# 105358-3SC002-01-A_PWR_MGMT.net
KiCad netlist of a schematic drawn in Altium Designer
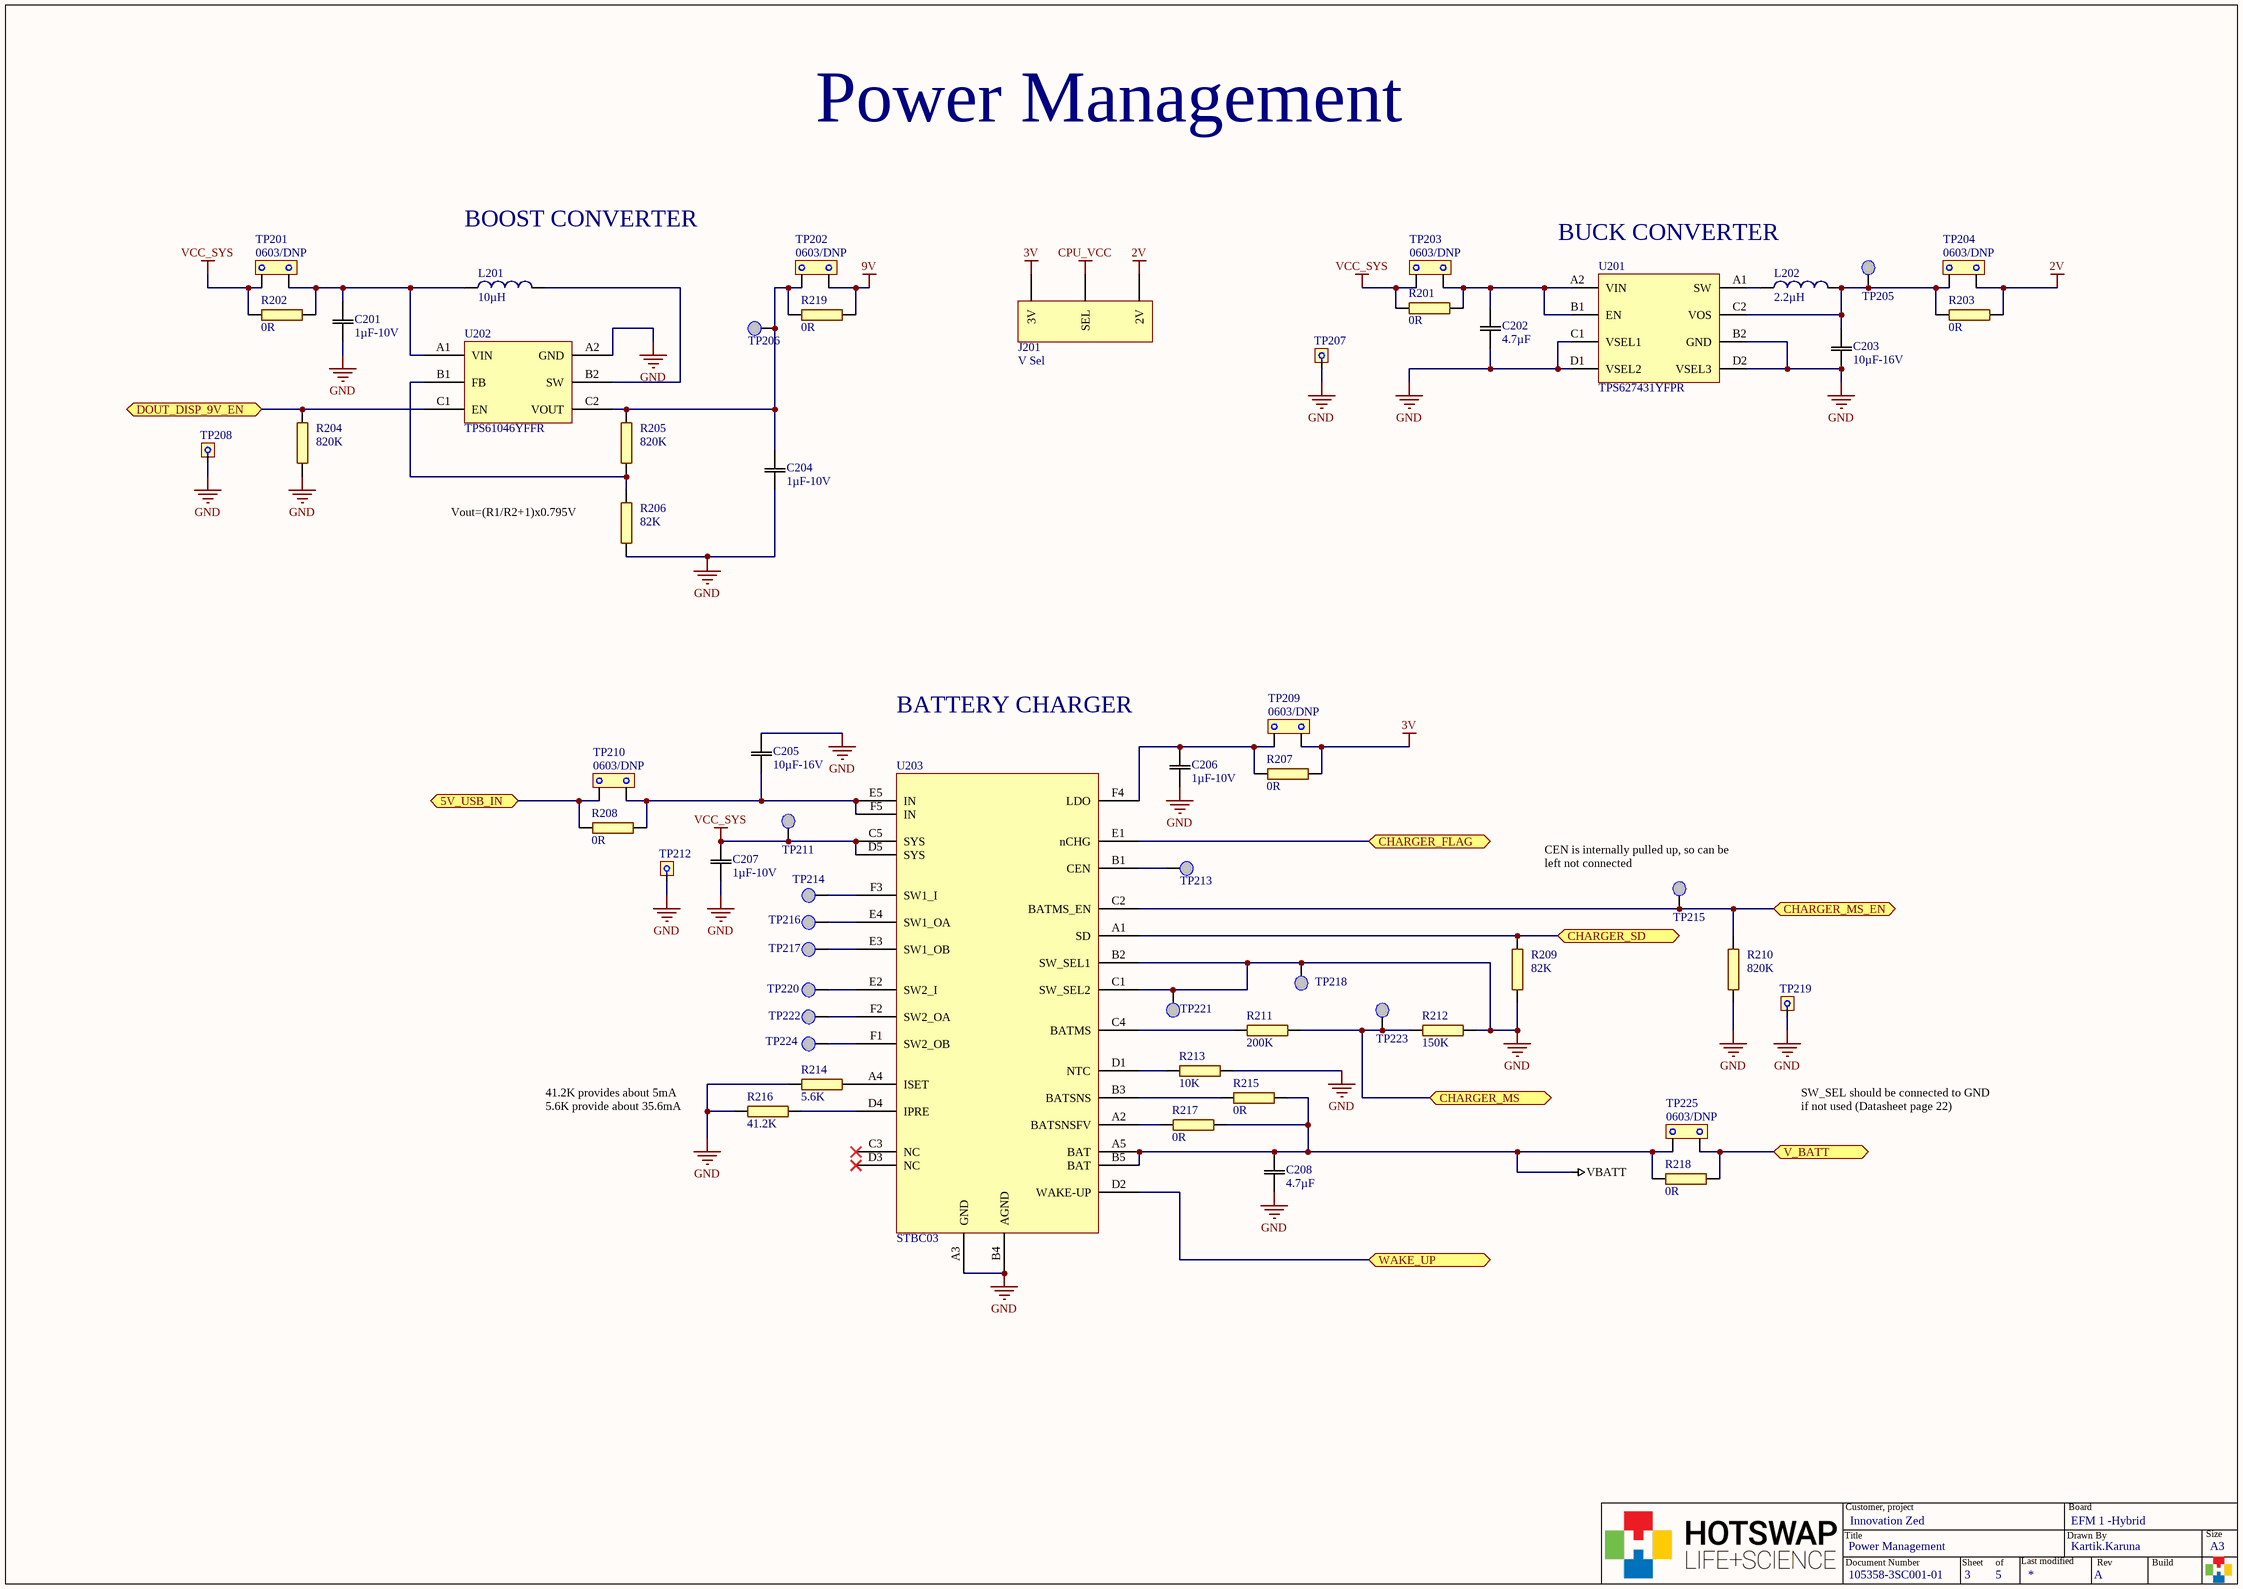
[diagram p0: 105358-3SC002-01-A_PWR_MGMT.SchDoc]

(export (version "E")
  (design (tool "Eeschema 10.0.6"))
  (components
    (comp (ref "C201")
      (value "1µF-10V")
      (footprint "0402C_HIGH_DENSITY")
      (description "1µF ±10% 10V X5R Ceramic Capacitor 0402")
      (fields
        (field (name "MANUFACTURER PART NUMBER") "CC0402KRX5R6BB105")
        (field (name "MANUFACTURER") "Yageo")
      )
      (libsource (lib "ConnectMedical") (part "0402C-1uF-10V"))
    )
    (comp (ref "C202")
      (value "4.7µF")
      (footprint "0402C_HIGH_DENSITY")
      (description "4.7µF ±10% 6.3V X5R Ceramic Capacitor 0402")
      (fields
        (field (name "MANUFACTURER PART NUMBER") "C1005X5R0J475K050BC")
        (field (name "MANUFACTURER") "TDK Corporation")
      )
      (libsource (lib "ConnectMedical") (part "0402C-4.7uF-6.3V"))
    )
    (comp (ref "C203")
      (value "10µF-16V")
      (footprint "0603C_HIGH_DENSITY")
      (description "16µF ±10% 16V X5R Ceramic Capacitor 0603")
      (fields
        (field (name "MANUFACTURER PART NUMBER") "GRT188R61C106KE13D")
        (field (name "MANUFACTURER") "Murata Electronics North America")
      )
      (libsource (lib "ConnectMedical") (part "0603C-10uF-16V"))
    )
    (comp (ref "C204")
      (value "1µF-10V")
      (footprint "0402C_HIGH_DENSITY")
      (description "1µF ±10% 10V X5R Ceramic Capacitor 0402")
      (fields
        (field (name "MANUFACTURER PART NUMBER") "CC0402KRX5R6BB105")
        (field (name "MANUFACTURER") "Yageo")
      )
      (libsource (lib "ConnectMedical") (part "0402C-1uF-10V"))
    )
    (comp (ref "C205")
      (value "10µF-16V")
      (footprint "0603C_HIGH_DENSITY")
      (description "16µF ±10% 16V X5R Ceramic Capacitor 0603")
      (fields
        (field (name "MANUFACTURER PART NUMBER") "GRT188R61C106KE13D")
        (field (name "MANUFACTURER") "Murata Electronics North America")
      )
      (libsource (lib "ConnectMedical") (part "0603C-10uF-16V"))
    )
    (comp (ref "C206")
      (value "1µF-10V")
      (footprint "0402C_HIGH_DENSITY")
      (description "1µF ±10% 10V X5R Ceramic Capacitor 0402")
      (fields
        (field (name "MANUFACTURER PART NUMBER") "CC0402KRX5R6BB105")
        (field (name "MANUFACTURER") "Yageo")
      )
      (libsource (lib "ConnectMedical") (part "0402C-1uF-10V"))
    )
    (comp (ref "C207")
      (value "1µF-10V")
      (footprint "0402C_HIGH_DENSITY")
      (description "1µF ±10% 10V X5R Ceramic Capacitor 0402")
      (fields
        (field (name "MANUFACTURER PART NUMBER") "CC0402KRX5R6BB105")
        (field (name "MANUFACTURER") "Yageo")
      )
      (libsource (lib "ConnectMedical") (part "0402C-1uF-10V"))
    )
    (comp (ref "C208")
      (value "4.7µF")
      (footprint "0402C_HIGH_DENSITY")
      (description "4.7µF ±10% 6.3V X5R Ceramic Capacitor 0402")
      (fields
        (field (name "MANUFACTURER PART NUMBER") "C1005X5R0J475K050BC")
        (field (name "MANUFACTURER") "TDK Corporation")
      )
      (libsource (lib "ConnectMedical") (part "0402C-4.7uF-6.3V"))
    )
    (comp (ref "J201")
      (value "V Sel")
      (footprint "Pin Header 3 x 1 - 2.54mm")
      (libsource (lib "ConnectMedical") (part "CPU_V_SEL"))
    )
    (comp (ref "L201")
      (value "10µH")
      (footprint "0805L_HIGH_DENSITY")
      (description "FIXED IND 10UH 500MA 300 MOHM")
      (fields
        (field (name "DIGI-KEY PART NUMBER") "445-6762-1-ND")
        (field (name "MANUFACTURER") "TDK Corporation")
      )
      (libsource (lib "ConnectMedical") (part "0805L-10uH-0.39Ohm"))
    )
    (comp (ref "L202")
      (value "2.2µH")
      (footprint "0805L_HIGH_DENSITY")
      (description "FIXED IND 2.2UH 600MA 0.2OHM SMD")
      (fields
        (field (name "DIGI-KEY PART NUMBER") "445-17077-1-ND")
        (field (name "MANUFACTURER") "TDK Corporation")
      )
      (libsource (lib "ConnectMedical") (part "0805L-2.2uH-0.2Ohm"))
    )
    (comp (ref "R201")
      (value "0R")
      (footprint "0603R-GENRIC")
      (description "RES SMD 0 OHM 1% 1/10W 0603")
      (fields (field (name "POWER") "0.063W"))
      (libsource (lib "ConnectMedical") (part "0603R-0R -1%-0.063W"))
    )
    (comp (ref "R202")
      (value "0R")
      (footprint "0603R-GENRIC")
      (description "RES SMD 0 OHM 1% 1/10W 0603")
      (fields (field (name "POWER") "0.063W"))
      (libsource (lib "ConnectMedical") (part "0603R-0R -1%-0.063W"))
    )
    (comp (ref "R203")
      (value "0R")
      (footprint "0603R-GENRIC")
      (description "RES SMD 0 OHM 1% 1/10W 0603")
      (fields (field (name "POWER") "0.063W"))
      (libsource (lib "ConnectMedical") (part "0603R-0R -1%-0.063W"))
    )
    (comp (ref "R204")
      (value "820K")
      (footprint "0402R-GENERIC")
      (description "RES SMD 820kOHM 1% 1/16W 0402")
      (fields (field (name "DIGI-KEY PART NUMBER") "YAG3240CT-ND") (field (name "MANUFACTURER") "Yageo"))
      (libsource (lib "ConnectMedical") (part "0402R-820k OHM-1%-0.063W"))
    )
    (comp (ref "R205")
      (value "820K")
      (footprint "0402R-GENERIC")
      (description "RES SMD 820kOHM 1% 1/16W 0402")
      (fields (field (name "DIGI-KEY PART NUMBER") "YAG3240CT-ND") (field (name "MANUFACTURER") "Yageo"))
      (libsource (lib "ConnectMedical") (part "0402R-820k OHM-1%-0.063W"))
    )
    (comp (ref "R206")
      (value "82K")
      (footprint "0402R-GENERIC")
      (description "RES SMD 82kOHM 1% 1/16W 0402")
      (fields (field (name "DIGI-KEY PART NUMBER") "311-82.0KLRCT-ND") (field (name "MANUFACTURER") "Yageo"))
      (libsource (lib "ConnectMedical") (part "0402R-82k OHM-1%-0.063W"))
    )
    (comp (ref "R207")
      (value "0R")
      (footprint "0603R-GENRIC")
      (description "RES SMD 0 OHM 1% 1/10W 0603")
      (fields (field (name "POWER") "0.063W"))
      (libsource (lib "ConnectMedical") (part "0603R-0R -1%-0.063W"))
    )
    (comp (ref "R208")
      (value "0R")
      (footprint "0603R-GENRIC")
      (description "RES SMD 0 OHM 1% 1/10W 0603")
      (fields (field (name "POWER") "0.063W"))
      (libsource (lib "ConnectMedical") (part "0603R-0R -1%-0.063W"))
    )
    (comp (ref "R209")
      (value "82K")
      (footprint "0402R-GENERIC")
      (description "RES SMD 82kOHM 1% 1/16W 0402")
      (fields (field (name "DIGI-KEY PART NUMBER") "311-82.0KLRCT-ND") (field (name "MANUFACTURER") "Yageo"))
      (libsource (lib "ConnectMedical") (part "0402R-82k OHM-1%-0.063W"))
    )
    (comp (ref "R210")
      (value "820K")
      (footprint "0402R-GENERIC")
      (description "RES SMD 820kOHM 1% 1/16W 0402")
      (fields (field (name "DIGI-KEY PART NUMBER") "YAG3240CT-ND") (field (name "MANUFACTURER") "Yageo"))
      (libsource (lib "ConnectMedical") (part "0402R-820k OHM-1%-0.063W"))
    )
    (comp (ref "R211")
      (value "200K")
      (footprint "0402R-GENERIC")
      (description "RES SMD 200kOHM 1% 1/16W 0402")
      (fields (field (name "DIGI-KEY PART NUMBER") "YAG3452CT-ND") (field (name "MANUFACTURER") "Yageo"))
      (libsource (lib "ConnectMedical") (part "0402R-200k OHM-1%-0.063W"))
    )
    (comp (ref "R212")
      (value "150K")
      (footprint "0402R-GENERIC")
      (description "RES SMD 150kOHM 5% 1/16W 0402")
      (fields (field (name "DIGI-KEY PART NUMBER") "311-150KJRCT-ND") (field (name "MANUFACTURER") "Yageo"))
      (libsource (lib "ConnectMedical") (part "0402R-150k OHM-5%-0.063W"))
    )
    (comp (ref "R213")
      (value "10K")
      (footprint "0402R-GENERIC")
      (description "RES SMD 10kOHM 1% 1/16W 0402")
      (fields (field (name "DIGI-KEY PART NUMBER") "311-10.0KLRCT-ND") (field (name "MANUFACTURER") "Yageo"))
      (libsource (lib "ConnectMedical") (part "0402R-10k OHM-1%-0.063W"))
    )
    (comp (ref "R214")
      (value "5.6K")
      (footprint "0603R-GENRIC")
      (description "RES SMD 5.6kOHM 5% 1/16W 0603")
      (fields (field (name "MANUFACTURER") "Yageo") (field (name "TOLERANCE") "5%"))
      (libsource (lib "ConnectMedical") (part "0603R-5.6k OHM-5%-0.063W"))
    )
    (comp (ref "R215")
      (value "0R")
      (footprint "0603R-GENRIC")
      (description "RES SMD 0 OHM 1% 1/10W 0603")
      (fields (field (name "POWER") "0.063W"))
      (libsource (lib "ConnectMedical") (part "0603R-0R -1%-0.063W"))
    )
    (comp (ref "R216")
      (value "41.2K")
      (footprint "0603R-GENRIC")
      (description "RES SMD 41.2kOHM 1% 0603")
      (fields (field (name "MANUFACTURER") "Yageo") (field (name "TOLERANCE") "1%"))
      (libsource (lib "ConnectMedical") (part "0603R-41.2k OHM-1%"))
    )
    (comp (ref "R217")
      (value "0R")
      (footprint "0603R-GENRIC")
      (description "RES SMD 0 OHM 1% 1/10W 0603")
      (fields (field (name "POWER") "0.063W"))
      (libsource (lib "ConnectMedical") (part "0603R-0R -1%-0.063W"))
    )
    (comp (ref "R218")
      (value "0R")
      (footprint "0603R-GENRIC")
      (description "RES SMD 0 OHM 1% 1/10W 0603")
      (fields (field (name "POWER") "0.063W"))
      (libsource (lib "ConnectMedical") (part "0603R-0R -1%-0.063W"))
    )
    (comp (ref "R219")
      (value "0R")
      (footprint "0603R-GENRIC")
      (description "RES SMD 0 OHM 1% 1/10W 0603")
      (fields (field (name "POWER") "0.063W"))
      (libsource (lib "ConnectMedical") (part "0603R-0R -1%-0.063W"))
    )
    (comp (ref "TP201")
      (value "0603/DNP")
      (footprint "TESTPOINT_C_R0608")
      (description "Test point for Med Current 0402 JUMPER SMD O OHM 1% 1/4W 0603")
      (libsource (lib "ConnectMedical") (part "TP_C_R0603"))
    )
    (comp (ref "TP202")
      (value "0603/DNP")
      (footprint "TESTPOINT_C_R0608")
      (description "Test point for Med Current 0402 JUMPER SMD O OHM 1% 1/4W 0603")
      (libsource (lib "ConnectMedical") (part "TP_C_R0603"))
    )
    (comp (ref "TP203")
      (value "0603/DNP")
      (footprint "TESTPOINT_C_R0608")
      (description "Test point for Med Current 0402 JUMPER SMD O OHM 1% 1/4W 0603")
      (libsource (lib "ConnectMedical") (part "TP_C_R0603"))
    )
    (comp (ref "TP204")
      (value "0603/DNP")
      (footprint "TESTPOINT_C_R0608")
      (description "Test point for Med Current 0402 JUMPER SMD O OHM 1% 1/4W 0603")
      (libsource (lib "ConnectMedical") (part "TP_C_R0603"))
    )
    (comp (ref "TP205")
      (value "TEST POINT")
      (footprint "PAD TEST POINT")
      (description "Testing Poiny")
      (libsource (lib "ConnectMedical") (part "TEST POINT"))
    )
    (comp (ref "TP206")
      (value "TEST POINT")
      (footprint "PAD TEST POINT")
      (description "Testing Poiny")
      (libsource (lib "ConnectMedical") (part "TEST POINT"))
    )
    (comp (ref "TP207")
      (value "TP_V_HOOK")
      (footprint "Testpoint_Hook")
      (description "Black PC Test Point")
      (fields
        (field (name "DIGI-KEY PART NUMBER") "36-5001-ND")
        (field (name "MANUFACTURER") "Keystone Electronics")
      )
      (libsource (lib "ConnectMedical") (part "TP_V_HOOK"))
    )
    (comp (ref "TP208")
      (value "TP_V_HOOK")
      (footprint "Testpoint_Hook")
      (description "Black PC Test Point")
      (fields
        (field (name "DIGI-KEY PART NUMBER") "36-5001-ND")
        (field (name "MANUFACTURER") "Keystone Electronics")
      )
      (libsource (lib "ConnectMedical") (part "TP_V_HOOK"))
    )
    (comp (ref "TP209")
      (value "0603/DNP")
      (footprint "TESTPOINT_C_R0608")
      (description "Test point for Med Current 0402 JUMPER SMD O OHM 1% 1/4W 0603")
      (libsource (lib "ConnectMedical") (part "TP_C_R0603"))
    )
    (comp (ref "TP210")
      (value "0603/DNP")
      (footprint "TESTPOINT_C_R0608")
      (description "Test point for Med Current 0402 JUMPER SMD O OHM 1% 1/4W 0603")
      (libsource (lib "ConnectMedical") (part "TP_C_R0603"))
    )
    (comp (ref "TP211")
      (value "TEST POINT")
      (footprint "PAD TEST POINT")
      (description "Testing Poiny")
      (libsource (lib "ConnectMedical") (part "TEST POINT"))
    )
    (comp (ref "TP212")
      (value "TP_V_HOOK")
      (footprint "Testpoint_Hook")
      (description "Black PC Test Point")
      (fields
        (field (name "DIGI-KEY PART NUMBER") "36-5001-ND")
        (field (name "MANUFACTURER") "Keystone Electronics")
      )
      (libsource (lib "ConnectMedical") (part "TP_V_HOOK"))
    )
    (comp (ref "TP213")
      (value "TEST POINT")
      (footprint "PAD TEST POINT")
      (description "Testing Poiny")
      (libsource (lib "ConnectMedical") (part "TEST POINT"))
    )
    (comp (ref "TP214")
      (value "TEST POINT")
      (footprint "PAD TEST POINT")
      (description "Testing Poiny")
      (libsource (lib "ConnectMedical") (part "TEST POINT"))
    )
    (comp (ref "TP215")
      (value "TEST POINT")
      (footprint "PAD TEST POINT")
      (description "Testing Poiny")
      (libsource (lib "ConnectMedical") (part "TEST POINT"))
    )
    (comp (ref "TP216")
      (value "TEST POINT")
      (footprint "PAD TEST POINT")
      (description "Testing Poiny")
      (libsource (lib "ConnectMedical") (part "TEST POINT"))
    )
    (comp (ref "TP217")
      (value "TEST POINT")
      (footprint "PAD TEST POINT")
      (description "Testing Poiny")
      (libsource (lib "ConnectMedical") (part "TEST POINT"))
    )
    (comp (ref "TP218")
      (value "TEST POINT")
      (footprint "PAD TEST POINT")
      (description "Testing Poiny")
      (libsource (lib "ConnectMedical") (part "TEST POINT"))
    )
    (comp (ref "TP219")
      (value "TP_V_HOOK")
      (footprint "Testpoint_Hook")
      (description "Black PC Test Point")
      (fields
        (field (name "DIGI-KEY PART NUMBER") "36-5001-ND")
        (field (name "MANUFACTURER") "Keystone Electronics")
      )
      (libsource (lib "ConnectMedical") (part "TP_V_HOOK"))
    )
    (comp (ref "TP220")
      (value "TEST POINT")
      (footprint "PAD TEST POINT")
      (description "Testing Poiny")
      (libsource (lib "ConnectMedical") (part "TEST POINT"))
    )
    (comp (ref "TP221")
      (value "TEST POINT")
      (footprint "PAD TEST POINT")
      (description "Testing Poiny")
      (libsource (lib "ConnectMedical") (part "TEST POINT"))
    )
    (comp (ref "TP222")
      (value "TEST POINT")
      (footprint "PAD TEST POINT")
      (description "Testing Poiny")
      (libsource (lib "ConnectMedical") (part "TEST POINT"))
    )
    (comp (ref "TP223")
      (value "TEST POINT")
      (footprint "PAD TEST POINT")
      (description "Testing Poiny")
      (libsource (lib "ConnectMedical") (part "TEST POINT"))
    )
    (comp (ref "TP224")
      (value "TEST POINT")
      (footprint "PAD TEST POINT")
      (description "Testing Poiny")
      (libsource (lib "ConnectMedical") (part "TEST POINT"))
    )
    (comp (ref "TP225")
      (value "0603/DNP")
      (footprint "TESTPOINT_C_R0608")
      (description "Test point for Med Current 0402 JUMPER SMD O OHM 1% 1/4W 0603")
      (libsource (lib "ConnectMedical") (part "TP_C_R0603"))
    )
    (comp (ref "U201")
      (value "TPS627431YFPR")
      (footprint "TPS627431YFPR")
      (description "Buck Converter")
      (fields
        (field (name "MANUFACTURER") "Texas Instruments")
        (field (name "DIGI-KEY PART NUMBER") "296-44499-2-ND")
      )
      (libsource (lib "ConnectMedical") (part "TPS627431YFPR"))
    )
    (comp (ref "U202")
      (value "TPS61046YFFR")
      (footprint "TPS61046YFFR")
      (description "Boost converter 28V")
      (fields
        (field (name "MANUFACTURER") "Texas Instruments")
        (field (name "DIGI-KEY PART NUMBER") "296-44337-1-ND")
      )
      (libsource (lib "ConnectMedical") (part "TPS61046YFFR"))
    )
    (comp (ref "U203")
      (value "STBC03")
      (footprint "STBC03")
      (description "Li-Ion linear battery charger")
      (fields
        (field (name "MANUFACTURER PART NUMBER") "STBC03JR")
        (field (name "MANUFACTURER") "STMicroelectronics")
      )
      (libsource (lib "ConnectMedical") (part "STBC03"))
    )
  )
  (nets
    (net (code "1") (name "/5V_USB_IN") (class "Default")
      (node (ref "R208") (pin "1") (pintype "passive"))
      (node (ref "TP210") (pin "1") (pintype "power_in"))
    )
    (net (code "2") (name "/CHARGER_FLAG") (class "Default")
      (node (ref "U203") (pin "E1") (pinfunction "nCHG_E1") (pintype "passive"))
    )
    (net (code "3") (name "/CHARGER_MS") (class "Default")
      (node (ref "R211") (pin "2") (pintype "passive"))
      (node (ref "R212") (pin "1") (pintype "passive"))
      (node (ref "TP223") (pin "1") (pinfunction "Test_Point_1") (pintype "passive"))
    )
    (net (code "4") (name "/CHARGER_MS_EN") (class "Default")
      (node (ref "R210") (pin "1") (pintype "passive"))
      (node (ref "TP215") (pin "1") (pinfunction "Test_Point_1") (pintype "passive"))
      (node (ref "U203") (pin "C2") (pinfunction "BATMS_EN_C2") (pintype "passive"))
    )
    (net (code "5") (name "/CHARGER_SD") (class "Default")
      (node (ref "R209") (pin "1") (pintype "passive"))
      (node (ref "U203") (pin "A1") (pinfunction "SD_A1") (pintype "passive"))
    )
    (net (code "6") (name "/DOUT_DISP_9V_EN") (class "Default")
      (node (ref "R204") (pin "1") (pintype "passive"))
      (node (ref "U202") (pin "C1") (pinfunction "EN_C1") (pintype "passive"))
    )
    (net (code "7") (name "/V_BATT") (class "Default")
      (node (ref "R218") (pin "2") (pintype "passive"))
      (node (ref "TP225") (pin "2") (pintype "power_in"))
    )
    (net (code "8") (name "/WAKE_UP") (class "Default")
      (node (ref "U203") (pin "D2") (pinfunction "WAKE-UP_D2") (pintype "passive"))
    )
    (net (code "9") (name "2V") (class "Default")
      (node (ref "J201") (pin "3") (pinfunction "2V_3") (pintype "power_in"))
      (node (ref "R203") (pin "2") (pintype "passive"))
      (node (ref "TP204") (pin "2") (pintype "power_in"))
    )
    (net (code "10") (name "3V") (class "Default")
      (node (ref "J201") (pin "1") (pinfunction "3V_1") (pintype "power_in"))
      (node (ref "R207") (pin "2") (pintype "passive"))
      (node (ref "TP209") (pin "2") (pintype "power_in"))
    )
    (net (code "11") (name "9V") (class "Default")
      (node (ref "R219") (pin "2") (pintype "passive"))
      (node (ref "TP202") (pin "2") (pintype "power_in"))
    )
    (net (code "12") (name "CPU_VCC") (class "Default")
      (node (ref "J201") (pin "2") (pinfunction "SEL_2") (pintype "power_in"))
    )
    (net (code "13") (name "GND") (class "Default")
      (node (ref "C201") (pin "1") (pinfunction "1_1") (pintype "passive"))
      (node (ref "C202") (pin "1") (pinfunction "1_1") (pintype "passive"))
      (node (ref "C203") (pin "1") (pinfunction "1_1") (pintype "passive"))
      (node (ref "C204") (pin "1") (pinfunction "1_1") (pintype "passive"))
      (node (ref "C205") (pin "2") (pinfunction "2_2") (pintype "passive"))
      (node (ref "C206") (pin "1") (pinfunction "1_1") (pintype "passive"))
      (node (ref "C207") (pin "1") (pinfunction "1_1") (pintype "passive"))
      (node (ref "C208") (pin "1") (pinfunction "1_1") (pintype "passive"))
      (node (ref "R204") (pin "2") (pintype "passive"))
      (node (ref "R206") (pin "2") (pintype "passive"))
      (node (ref "R209") (pin "2") (pintype "passive"))
      (node (ref "R210") (pin "2") (pintype "passive"))
      (node (ref "R212") (pin "2") (pintype "passive"))
      (node (ref "R213") (pin "2") (pintype "passive"))
      (node (ref "R214") (pin "1") (pintype "passive"))
      (node (ref "R216") (pin "1") (pintype "passive"))
      (node (ref "TP207") (pin "1") (pinfunction "8_1") (pintype "passive"))
      (node (ref "TP208") (pin "1") (pinfunction "8_1") (pintype "passive"))
      (node (ref "TP212") (pin "1") (pinfunction "8_1") (pintype "passive"))
      (node (ref "TP218") (pin "1") (pinfunction "Test_Point_1") (pintype "passive"))
      (node (ref "TP219") (pin "1") (pinfunction "8_1") (pintype "passive"))
      (node (ref "TP221") (pin "1") (pinfunction "Test_Point_1") (pintype "passive"))
      (node (ref "U201") (pin "B2") (pinfunction "GND_B2") (pintype "passive"))
      (node (ref "U201") (pin "C1") (pinfunction "VSEL1_C1") (pintype "passive"))
      (node (ref "U201") (pin "D1") (pinfunction "VSEL2_D1") (pintype "passive"))
      (node (ref "U201") (pin "D2") (pinfunction "VSEL3_D2") (pintype "passive"))
      (node (ref "U202") (pin "A2") (pinfunction "GND_A2") (pintype "passive"))
      (node (ref "U203") (pin "A3") (pinfunction "GND_A3") (pintype "passive"))
      (node (ref "U203") (pin "B2") (pinfunction "SW_SEL1_B2") (pintype "passive"))
      (node (ref "U203") (pin "B4") (pinfunction "AGND_B4") (pintype "passive"))
      (node (ref "U203") (pin "C1") (pinfunction "SW_SEL2_C1") (pintype "passive"))
    )
    (net (code "14") (name "Net-(C205-Pad1)") (class "Default")
      (node (ref "C205") (pin "1") (pinfunction "1_1") (pintype "passive"))
      (node (ref "R208") (pin "2") (pintype "passive"))
      (node (ref "TP210") (pin "2") (pintype "power_in"))
      (node (ref "U203") (pin "E5") (pinfunction "IN_E5") (pintype "passive"))
      (node (ref "U203") (pin "F5") (pinfunction "IN_F5") (pintype "passive"))
    )
    (net (code "15") (name "Net-(TP205-Test_Point)") (class "Default")
      (node (ref "C203") (pin "2") (pinfunction "2_2") (pintype "passive"))
      (node (ref "L202") (pin "2") (pinfunction "2_2") (pintype "passive"))
      (node (ref "R203") (pin "1") (pintype "passive"))
      (node (ref "TP204") (pin "1") (pintype "power_in"))
      (node (ref "TP205") (pin "1") (pinfunction "Test_Point_1") (pintype "passive"))
      (node (ref "U201") (pin "C2") (pinfunction "VOS_C2") (pintype "passive"))
    )
    (net (code "16") (name "Net-(TP206-Test_Point)") (class "Default")
      (node (ref "C204") (pin "2") (pinfunction "2_2") (pintype "passive"))
      (node (ref "R205") (pin "1") (pintype "passive"))
      (node (ref "R219") (pin "1") (pintype "passive"))
      (node (ref "TP202") (pin "1") (pintype "power_in"))
      (node (ref "TP206") (pin "1") (pinfunction "Test_Point_1") (pintype "passive"))
      (node (ref "U202") (pin "C2") (pinfunction "VOUT_C2") (pintype "passive"))
    )
    (net (code "17") (name "Net-(TP213-Test_Point)") (class "Default")
      (node (ref "TP213") (pin "1") (pinfunction "Test_Point_1") (pintype "passive"))
      (node (ref "U203") (pin "B1") (pinfunction "CEN_B1") (pintype "passive"))
    )
    (net (code "18") (name "Net-(TP214-Test_Point)") (class "Default")
      (node (ref "TP214") (pin "1") (pinfunction "Test_Point_1") (pintype "passive"))
      (node (ref "U203") (pin "F3") (pinfunction "SW1_I_F3") (pintype "passive"))
    )
    (net (code "19") (name "Net-(TP216-Test_Point)") (class "Default")
      (node (ref "TP216") (pin "1") (pinfunction "Test_Point_1") (pintype "passive"))
      (node (ref "U203") (pin "E4") (pinfunction "SW1_OA_E4") (pintype "passive"))
    )
    (net (code "20") (name "Net-(TP217-Test_Point)") (class "Default")
      (node (ref "TP217") (pin "1") (pinfunction "Test_Point_1") (pintype "passive"))
      (node (ref "U203") (pin "E3") (pinfunction "SW1_OB_E3") (pintype "passive"))
    )
    (net (code "21") (name "Net-(TP220-Test_Point)") (class "Default")
      (node (ref "TP220") (pin "1") (pinfunction "Test_Point_1") (pintype "passive"))
      (node (ref "U203") (pin "E2") (pinfunction "SW2_I_E2") (pintype "passive"))
    )
    (net (code "22") (name "Net-(TP222-Test_Point)") (class "Default")
      (node (ref "TP222") (pin "1") (pinfunction "Test_Point_1") (pintype "passive"))
      (node (ref "U203") (pin "F2") (pinfunction "SW2_OA_F2") (pintype "passive"))
    )
    (net (code "23") (name "Net-(TP224-Test_Point)") (class "Default")
      (node (ref "TP224") (pin "1") (pinfunction "Test_Point_1") (pintype "passive"))
      (node (ref "U203") (pin "F1") (pinfunction "SW2_OB_F1") (pintype "passive"))
    )
    (net (code "24") (name "Net-(U201-EN)") (class "Default")
      (node (ref "C202") (pin "2") (pinfunction "2_2") (pintype "passive"))
      (node (ref "R201") (pin "2") (pintype "passive"))
      (node (ref "TP203") (pin "2") (pintype "power_in"))
      (node (ref "U201") (pin "A2") (pinfunction "VIN_A2") (pintype "passive"))
      (node (ref "U201") (pin "B1") (pinfunction "EN_B1") (pintype "passive"))
    )
    (net (code "25") (name "Net-(U201-SW)") (class "Default")
      (node (ref "L202") (pin "1") (pinfunction "1_1") (pintype "passive"))
      (node (ref "U201") (pin "A1") (pinfunction "SW_A1") (pintype "passive"))
    )
    (net (code "26") (name "Net-(U202-FB)") (class "Default")
      (node (ref "R205") (pin "2") (pintype "passive"))
      (node (ref "R206") (pin "1") (pintype "passive"))
      (node (ref "U202") (pin "B1") (pinfunction "FB_B1") (pintype "passive"))
    )
    (net (code "27") (name "Net-(U202-SW)") (class "Default")
      (node (ref "L201") (pin "2") (pinfunction "2_2") (pintype "passive"))
      (node (ref "U202") (pin "B2") (pinfunction "SW_B2") (pintype "passive"))
    )
    (net (code "28") (name "Net-(U202-VIN)") (class "Default")
      (node (ref "C201") (pin "2") (pinfunction "2_2") (pintype "passive"))
      (node (ref "L201") (pin "1") (pinfunction "1_1") (pintype "passive"))
      (node (ref "R202") (pin "2") (pintype "passive"))
      (node (ref "TP201") (pin "2") (pintype "power_in"))
      (node (ref "U202") (pin "A1") (pinfunction "VIN_A1") (pintype "passive"))
    )
    (net (code "29") (name "Net-(U203-BATMS)") (class "Default")
      (node (ref "R211") (pin "1") (pintype "passive"))
      (node (ref "U203") (pin "C4") (pinfunction "BATMS_C4") (pintype "passive"))
    )
    (net (code "30") (name "Net-(U203-BATSNS)") (class "Default")
      (node (ref "R215") (pin "1") (pintype "passive"))
      (node (ref "U203") (pin "B3") (pinfunction "BATSNS_B3") (pintype "passive"))
    )
    (net (code "31") (name "Net-(U203-BATSNSFV)") (class "Default")
      (node (ref "R217") (pin "1") (pintype "passive"))
      (node (ref "U203") (pin "A2") (pinfunction "BATSNSFV_A2") (pintype "passive"))
    )
    (net (code "32") (name "Net-(U203-IPRE)") (class "Default")
      (node (ref "R216") (pin "2") (pintype "passive"))
      (node (ref "U203") (pin "D4") (pinfunction "IPRE_D4") (pintype "passive"))
    )
    (net (code "33") (name "Net-(U203-ISET)") (class "Default")
      (node (ref "R214") (pin "2") (pintype "passive"))
      (node (ref "U203") (pin "A4") (pinfunction "ISET_A4") (pintype "passive"))
    )
    (net (code "34") (name "Net-(U203-LDO)") (class "Default")
      (node (ref "C206") (pin "2") (pinfunction "2_2") (pintype "passive"))
      (node (ref "R207") (pin "1") (pintype "passive"))
      (node (ref "TP209") (pin "1") (pintype "power_in"))
      (node (ref "U203") (pin "F4") (pinfunction "LDO_F4") (pintype "passive"))
    )
    (net (code "35") (name "Net-(U203-NTC)") (class "Default")
      (node (ref "R213") (pin "1") (pintype "passive"))
      (node (ref "U203") (pin "D1") (pinfunction "NTC_D1") (pintype "passive"))
    )
    (net (code "36") (name "VBATT") (class "Default")
      (node (ref "C208") (pin "2") (pinfunction "2_2") (pintype "passive"))
      (node (ref "R215") (pin "2") (pintype "passive"))
      (node (ref "R217") (pin "2") (pintype "passive"))
      (node (ref "R218") (pin "1") (pintype "passive"))
      (node (ref "TP225") (pin "1") (pintype "power_in"))
      (node (ref "U203") (pin "A5") (pinfunction "BAT_A5") (pintype "passive"))
      (node (ref "U203") (pin "B5") (pinfunction "BAT_B5") (pintype "passive"))
    )
    (net (code "37") (name "VCC_SYS") (class "Default")
      (node (ref "C207") (pin "2") (pinfunction "2_2") (pintype "passive"))
      (node (ref "R201") (pin "1") (pintype "passive"))
      (node (ref "R202") (pin "1") (pintype "passive"))
      (node (ref "TP201") (pin "1") (pintype "power_in"))
      (node (ref "TP203") (pin "1") (pintype "power_in"))
      (node (ref "TP211") (pin "1") (pinfunction "Test_Point_1") (pintype "passive"))
      (node (ref "U203") (pin "C5") (pinfunction "SYS_C5") (pintype "passive"))
      (node (ref "U203") (pin "D5") (pinfunction "SYS_D5") (pintype "passive"))
    )
    (net (code "38") (name "unconnected-(U203-NC-PadC3)") (class "Default")
      (node (ref "U203") (pin "C3") (pinfunction "NC_C3") (pintype "passive+no_connect"))
    )
    (net (code "39") (name "unconnected-(U203-NC-PadD3)") (class "Default")
      (node (ref "U203") (pin "D3") (pinfunction "NC_D3") (pintype "passive+no_connect"))
    )
  )
)
